# ciclo_V2.net
KiCad netlist of a schematic drawn in Altium Designer
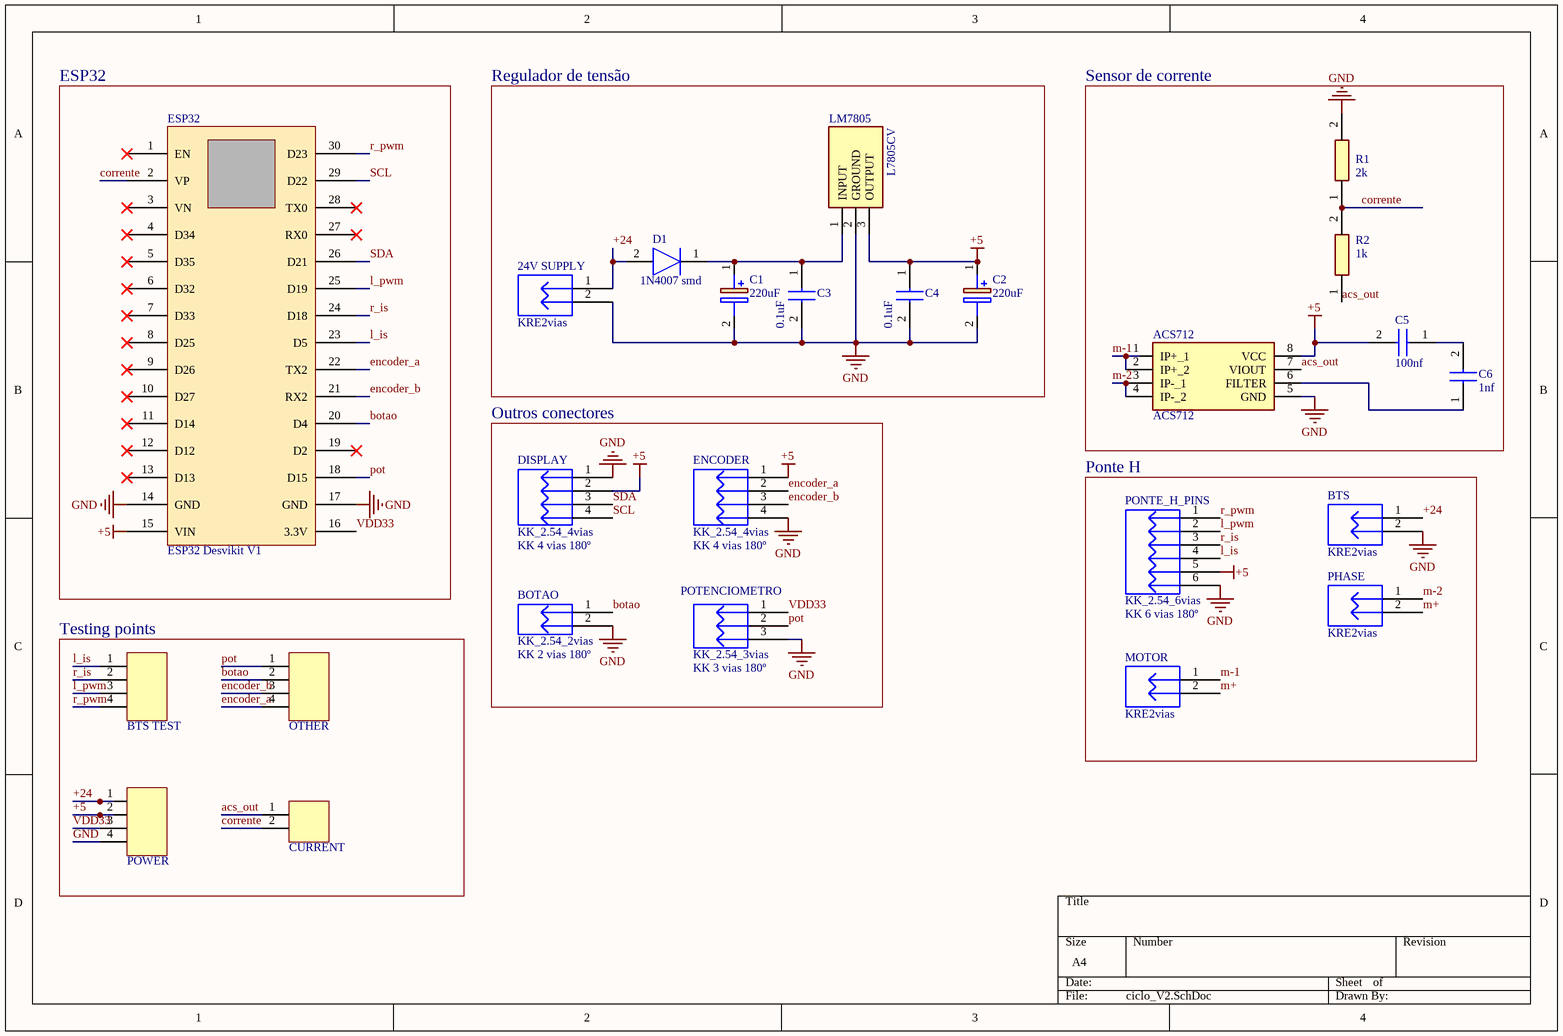
[diagram p0: ciclo_V2.SchDoc]

(export (version "E")
  (design (tool "Eeschema 10.0.6"))
  (components
    (comp (ref "24V SUPPLY")
      (value "KRE2vias")
      (footprint "KRE2-2vias")
      (description "Conector 2 vias")
      (libsource (lib "cicloV2_lib") (part "KRE2vias"))
    )
    (comp (ref "ACS712")
      (value "ACS712")
      (footprint "SOIC127P600X175-8N")
      (description "Sensor de corrente 20A")
      (fields (field (name "MANUFACTURER_PART_NUMBER") "ACS712ELCTR-05B-T"))
      (libsource (lib "cicloV2_lib") (part "ACS712"))
    )
    (comp (ref "BOTAO")
      (value "KK_2.54_2vias")
      (footprint "KK_2VIAS_180")
      (description "Conector KK 2.54mm 2 vias")
      (fields (field (name "VALOR") "KK 2 vias 180º"))
      (libsource (lib "cicloV2_lib") (part "KK_2.54_2vias"))
    )
    (comp (ref "BTS")
      (value "KRE2vias")
      (footprint "KRE2-2vias")
      (description "Conector 2 vias")
      (libsource (lib "cicloV2_lib") (part "KRE2vias"))
    )
    (comp (ref "BTS TEST")
      (value "Testing PADS 1x4")
      (footprint "Testing PADS 1x4")
      (description "Headers & Wire Housings 40Pin 2mm Spacing Single Row Hdrs, 5pc")
      (fields (field (name "MANUFACTURER") "Cromax"))
      (libsource (lib "cicloV2_lib") (part "Testing PADS 1x4"))
    )
    (comp (ref "C1")
      (value "220uF")
      (footprint "CAPPRD200W55D500H1200")
      (description "Capacitor Polarised")
      (fields
        (field (name "MANUFACTURER_PART_NUMBER") "ECA-0JM221")
        (field (name "MOUSER PART NUMBER") "667-ECA-0JM221")
      )
      (libsource (lib "cicloV2_lib") (part "Capacitor eletrolítico D5mm"))
    )
    (comp (ref "C2")
      (value "220uF")
      (footprint "CAPPRD200W55D500H1200")
      (description "Capacitor Polarised")
      (fields
        (field (name "MANUFACTURER_PART_NUMBER") "ECA-0JM221")
        (field (name "MOUSER PART NUMBER") "667-ECA-0JM221")
      )
      (libsource (lib "cicloV2_lib") (part "Capacitor eletrolítico D5mm"))
    )
    (comp (ref "C3")
      (value "0.1uF")
      (footprint "CAPC3216X180N")
      (description "Capacitor cerâmico SMD")
      (fields
        (field (name "MANUFACTURER_PART_NUMBER") "GRM31CC80E227ME11L")
        (field (name "MOUSER PART NUMBER") "81-GRM31CC80E227ME1L")
      )
      (libsource (lib "cicloV2_lib") (part "GRM31CC80E227ME11L"))
    )
    (comp (ref "C4")
      (value "0.1uF")
      (footprint "CAPC3216X180N")
      (description "Capacitor cerâmico SMD")
      (fields
        (field (name "MANUFACTURER_PART_NUMBER") "GRM31CC80E227ME11L")
        (field (name "MOUSER PART NUMBER") "81-GRM31CC80E227ME1L")
      )
      (libsource (lib "cicloV2_lib") (part "GRM31CC80E227ME11L"))
    )
    (comp (ref "C5")
      (value "100nf")
      (footprint "CAPC3216X180N")
      (description "Capacitor cerâmico SMD")
      (fields
        (field (name "MANUFACTURER_PART_NUMBER") "GRM31CC80E227ME11L")
        (field (name "MOUSER PART NUMBER") "81-GRM31CC80E227ME1L")
      )
      (libsource (lib "cicloV2_lib") (part "GRM31CC80E227ME11L"))
    )
    (comp (ref "C6")
      (value "1nf")
      (footprint "CAPC3216X180N")
      (description "Capacitor cerâmico SMD")
      (fields
        (field (name "MANUFACTURER_PART_NUMBER") "GRM31CC80E227ME11L")
        (field (name "MOUSER PART NUMBER") "81-GRM31CC80E227ME1L")
      )
      (libsource (lib "cicloV2_lib") (part "GRM31CC80E227ME11L"))
    )
    (comp (ref "CURRENT")
      (value "Testing PADS 1x2")
      (footprint "Testing PADS 1x2")
      (description "Headers & Wire Housings 40Pin 2mm Spacing Single Row Hdrs, 5pc")
      (fields (field (name "MANUFACTURER") "Cromax"))
      (libsource (lib "cicloV2_lib") (part "Testing PADS 1x2"))
    )
    (comp (ref "D1")
      (value "1N4007 smd")
      (footprint "cicloV2_lib:DIOM5327X242N")
      (description "Diode smd")
      (fields (field (name "MANUFACTURER_PART_NUMBER") "1N4007"))
      (libsource (lib "cicloV2_lib") (part "1N4007 smd"))
    )
    (comp (ref "DISPLAY")
      (value "KK_2.54_4vias")
      (footprint "KK_4vias_180")
      (description "Conector KK 2.54mm 4 vias")
      (fields (field (name "VALOR") "KK 4 vias 180º"))
      (libsource (lib "cicloV2_lib") (part "KK_2.54_4vias"))
    )
    (comp (ref "ENCODER")
      (value "KK_2.54_4vias")
      (footprint "KK_4vias_180")
      (description "Conector KK 2.54mm 4 vias")
      (fields (field (name "VALOR") "KK 4 vias 180º"))
      (libsource (lib "cicloV2_lib") (part "KK_2.54_4vias"))
    )
    (comp (ref "ESP32")
      (value "ESP32 Desvikit V1")
      (footprint "ESP32_Desvikit_v1")
      (description "microcontrolador com modulo bluetooth e wifi")
      (fields (field (name "Comment") "microcontrolador"))
      (libsource (lib "cicloV2_lib") (part "ESP32 Desvikit v1"))
    )
    (comp (ref "LM7805")
      (value "L7805CV")
      (footprint "TO255P460X1020X2008-3P")
      (description "Regulador de tensão para 5V")
      (fields (field (name "MOUSER PART NUMBER") "511-L7805CV"))
      (libsource (lib "cicloV2_lib") (part "L7805CV"))
    )
    (comp (ref "MOTOR")
      (value "KRE2vias")
      (footprint "KRE2-2vias")
      (description "Conector 2 vias")
      (libsource (lib "cicloV2_lib") (part "KRE2vias"))
    )
    (comp (ref "OTHER")
      (value "Testing PADS 1x4")
      (footprint "Testing PADS 1x4")
      (description "Headers & Wire Housings 40Pin 2mm Spacing Single Row Hdrs, 5pc")
      (fields (field (name "MANUFACTURER") "Cromax"))
      (libsource (lib "cicloV2_lib") (part "Testing PADS 1x4"))
    )
    (comp (ref "PHASE")
      (value "KRE2vias")
      (footprint "KRE2-2vias")
      (description "Conector 2 vias")
      (libsource (lib "cicloV2_lib") (part "KRE2vias"))
    )
    (comp (ref "PONTE_H_PINS")
      (value "KK_2.54_6vias")
      (footprint "KK_6vias_180")
      (description "Conector KK 2.54mm 6 vias")
      (fields (field (name "VALOR") "KK 6 vias 180º"))
      (libsource (lib "cicloV2_lib") (part "KK_2.54_6vias"))
    )
    (comp (ref "POTENCIOMETRO")
      (value "KK_2.54_3vias")
      (footprint "KK_3vias_180")
      (description "Conector KK 2.54mm 3 vias")
      (fields (field (name "VALOR") "KK 3 vias 180º"))
      (libsource (lib "cicloV2_lib") (part "KK_2.54_3vias"))
    )
    (comp (ref "POWER")
      (value "Testing PADS 1x4")
      (footprint "Testing PADS 1x4")
      (description "Headers & Wire Housings 40Pin 2mm Spacing Single Row Hdrs, 5pc")
      (fields (field (name "MANUFACTURER") "Cromax"))
      (libsource (lib "cicloV2_lib") (part "Testing PADS 1x4"))
    )
    (comp (ref "R1")
      (value "2k")
      (footprint "SamacSys:RESC3216X75N")
      (description "Resistor SMD 1206")
      (fields
        (field (name "MANUFACTURER_PART_NUMBER") "CR1206-F/-2R00ELF")
        (field (name "MOUSER PART NUMBER") "652-CR1206-F/2R00ELF")
      )
      (libsource (lib "cicloV2_lib") (part "CR1206"))
    )
    (comp (ref "R2")
      (value "1k")
      (footprint "SamacSys:RESC3216X75N")
      (description "Resistor SMD 1206")
      (fields
        (field (name "MANUFACTURER_PART_NUMBER") "CR1206-F/-2R00ELF")
        (field (name "MOUSER PART NUMBER") "652-CR1206-F/2R00ELF")
      )
      (libsource (lib "cicloV2_lib") (part "CR1206"))
    )
  )
  (nets
    (net (code "1") (name "+5") (class "Default")
      (node (ref "ACS712") (pin "8") (pinfunction "VCC_8") (pintype "passive"))
      (node (ref "C2") (pin "1") (pinfunction "+_1") (pintype "passive"))
      (node (ref "C4") (pin "1") (pinfunction "1_1") (pintype "passive"))
      (node (ref "C5") (pin "2") (pinfunction "2_2") (pintype "passive"))
      (node (ref "DISPLAY") (pin "2") (pintype "passive"))
      (node (ref "ENCODER") (pin "1") (pintype "passive"))
      (node (ref "ESP32") (pin "15") (pinfunction "VIN_15") (pintype "passive"))
      (node (ref "LM7805") (pin "3") (pinfunction "OUTPUT_3") (pintype "passive"))
      (node (ref "PONTE_H_PINS") (pin "5") (pintype "passive"))
      (node (ref "POWER") (pin "2") (pintype "passive"))
    )
    (net (code "2") (name "/+24") (class "Default")
      (node (ref "24V SUPPLY") (pin "1") (pintype "passive"))
      (node (ref "BTS") (pin "1") (pintype "passive"))
      (node (ref "D1") (pin "2") (pinfunction "A_2") (pintype "passive"))
      (node (ref "POWER") (pin "1") (pintype "passive"))
    )
    (net (code "3") (name "/SCL") (class "Default")
      (node (ref "DISPLAY") (pin "4") (pintype "passive"))
      (node (ref "ESP32") (pin "29") (pinfunction "D22_29") (pintype "passive"))
    )
    (net (code "4") (name "/SDA") (class "Default")
      (node (ref "DISPLAY") (pin "3") (pintype "passive"))
      (node (ref "ESP32") (pin "26") (pinfunction "D21_26") (pintype "passive"))
    )
    (net (code "5") (name "/VDD33") (class "Default")
      (node (ref "ESP32") (pin "16") (pinfunction "3.3V_16") (pintype "passive"))
      (node (ref "POTENCIOMETRO") (pin "1") (pintype "passive"))
      (node (ref "POWER") (pin "3") (pintype "passive"))
    )
    (net (code "6") (name "/acs_out") (class "Default")
      (node (ref "ACS712") (pin "7") (pinfunction "VIOUT_7") (pintype "passive"))
      (node (ref "CURRENT") (pin "1") (pintype "passive"))
      (node (ref "R2") (pin "1") (pinfunction "1_1") (pintype "passive"))
    )
    (net (code "7") (name "/botao") (class "Default")
      (node (ref "BOTAO") (pin "1") (pintype "passive"))
      (node (ref "ESP32") (pin "20") (pinfunction "D4_20") (pintype "passive"))
      (node (ref "OTHER") (pin "2") (pintype "passive"))
    )
    (net (code "8") (name "/corrente") (class "Default")
      (node (ref "CURRENT") (pin "2") (pintype "passive"))
      (node (ref "ESP32") (pin "2") (pinfunction "VP_2") (pintype "passive"))
      (node (ref "R1") (pin "1") (pinfunction "1_1") (pintype "passive"))
      (node (ref "R2") (pin "2") (pinfunction "2_2") (pintype "passive"))
    )
    (net (code "9") (name "/encoder_a") (class "Default")
      (node (ref "ENCODER") (pin "2") (pintype "passive"))
      (node (ref "ESP32") (pin "22") (pinfunction "TX2_22") (pintype "passive"))
      (node (ref "OTHER") (pin "4") (pintype "passive"))
    )
    (net (code "10") (name "/encoder_b") (class "Default")
      (node (ref "ENCODER") (pin "3") (pintype "passive"))
      (node (ref "ESP32") (pin "21") (pinfunction "RX2_21") (pintype "passive"))
      (node (ref "OTHER") (pin "3") (pintype "passive"))
    )
    (net (code "11") (name "/l_is") (class "Default")
      (node (ref "BTS TEST") (pin "1") (pintype "passive"))
      (node (ref "ESP32") (pin "23") (pinfunction "D5_23") (pintype "passive"))
      (node (ref "PONTE_H_PINS") (pin "4") (pintype "passive"))
    )
    (net (code "12") (name "/l_pwm") (class "Default")
      (node (ref "BTS TEST") (pin "3") (pintype "passive"))
      (node (ref "ESP32") (pin "25") (pinfunction "D19_25") (pintype "passive"))
      (node (ref "PONTE_H_PINS") (pin "2") (pintype "passive"))
    )
    (net (code "13") (name "/m+") (class "Default")
      (node (ref "MOTOR") (pin "2") (pintype "passive"))
      (node (ref "PHASE") (pin "2") (pintype "passive"))
    )
    (net (code "14") (name "/m-1") (class "Default")
      (node (ref "ACS712") (pin "1") (pinfunction "IP+_1_1") (pintype "passive"))
      (node (ref "ACS712") (pin "2") (pinfunction "IP+_2_2") (pintype "passive"))
      (node (ref "MOTOR") (pin "1") (pintype "passive"))
    )
    (net (code "15") (name "/m-2") (class "Default")
      (node (ref "ACS712") (pin "3") (pinfunction "IP-_1_3") (pintype "passive"))
      (node (ref "ACS712") (pin "4") (pinfunction "IP-_2_4") (pintype "passive"))
      (node (ref "PHASE") (pin "1") (pintype "passive"))
    )
    (net (code "16") (name "/pot") (class "Default")
      (node (ref "ESP32") (pin "18") (pinfunction "D15_18") (pintype "passive"))
      (node (ref "OTHER") (pin "1") (pintype "passive"))
      (node (ref "POTENCIOMETRO") (pin "2") (pintype "passive"))
    )
    (net (code "17") (name "/r_is") (class "Default")
      (node (ref "BTS TEST") (pin "2") (pintype "passive"))
      (node (ref "ESP32") (pin "24") (pinfunction "D18_24") (pintype "passive"))
      (node (ref "PONTE_H_PINS") (pin "3") (pintype "passive"))
    )
    (net (code "18") (name "/r_pwm") (class "Default")
      (node (ref "BTS TEST") (pin "4") (pintype "passive"))
      (node (ref "ESP32") (pin "30") (pinfunction "D23_30") (pintype "passive"))
      (node (ref "PONTE_H_PINS") (pin "1") (pintype "passive"))
    )
    (net (code "19") (name "GND") (class "Default")
      (node (ref "24V SUPPLY") (pin "2") (pintype "passive"))
      (node (ref "ACS712") (pin "5") (pinfunction "GND_5") (pintype "passive"))
      (node (ref "BOTAO") (pin "2") (pintype "passive"))
      (node (ref "BTS") (pin "2") (pintype "passive"))
      (node (ref "C1") (pin "2") (pinfunction "-_2") (pintype "passive"))
      (node (ref "C2") (pin "2") (pinfunction "-_2") (pintype "passive"))
      (node (ref "C3") (pin "2") (pinfunction "2_2") (pintype "passive"))
      (node (ref "C4") (pin "2") (pinfunction "2_2") (pintype "passive"))
      (node (ref "DISPLAY") (pin "1") (pintype "passive"))
      (node (ref "ENCODER") (pin "4") (pintype "passive"))
      (node (ref "ESP32") (pin "14") (pinfunction "GND_14") (pintype "passive"))
      (node (ref "ESP32") (pin "17") (pinfunction "GND_17") (pintype "passive"))
      (node (ref "LM7805") (pin "2") (pinfunction "GROUND_2") (pintype "passive"))
      (node (ref "PONTE_H_PINS") (pin "6") (pintype "passive"))
      (node (ref "POTENCIOMETRO") (pin "3") (pintype "passive"))
      (node (ref "POWER") (pin "4") (pintype "passive"))
      (node (ref "R1") (pin "2") (pinfunction "2_2") (pintype "passive"))
    )
    (net (code "20") (name "Net-(ACS712-FILTER)") (class "Default")
      (node (ref "ACS712") (pin "6") (pinfunction "FILTER_6") (pintype "passive"))
      (node (ref "C6") (pin "1") (pinfunction "1_1") (pintype "passive"))
    )
    (net (code "21") (name "Net-(C1-+)") (class "Default")
      (node (ref "C1") (pin "1") (pinfunction "+_1") (pintype "passive"))
      (node (ref "C3") (pin "1") (pinfunction "1_1") (pintype "passive"))
      (node (ref "D1") (pin "1") (pinfunction "K_1") (pintype "passive"))
      (node (ref "LM7805") (pin "1") (pinfunction "INPUT_1") (pintype "passive"))
    )
    (net (code "22") (name "Net-(C5-Pad1)") (class "Default")
      (node (ref "C5") (pin "1") (pinfunction "1_1") (pintype "passive"))
      (node (ref "C6") (pin "2") (pinfunction "2_2") (pintype "passive"))
    )
    (net (code "23") (name "unconnected-(ESP32-D2-Pad19)") (class "Default")
      (node (ref "ESP32") (pin "19") (pinfunction "D2_19") (pintype "passive+no_connect"))
    )
    (net (code "24") (name "unconnected-(ESP32-D12-Pad12)") (class "Default")
      (node (ref "ESP32") (pin "12") (pinfunction "D12_12") (pintype "passive+no_connect"))
    )
    (net (code "25") (name "unconnected-(ESP32-D13-Pad13)") (class "Default")
      (node (ref "ESP32") (pin "13") (pinfunction "D13_13") (pintype "passive+no_connect"))
    )
    (net (code "26") (name "unconnected-(ESP32-D14-Pad11)") (class "Default")
      (node (ref "ESP32") (pin "11") (pinfunction "D14_11") (pintype "passive+no_connect"))
    )
    (net (code "27") (name "unconnected-(ESP32-D25-Pad8)") (class "Default")
      (node (ref "ESP32") (pin "8") (pinfunction "D25_8") (pintype "passive+no_connect"))
    )
    (net (code "28") (name "unconnected-(ESP32-D26-Pad9)") (class "Default")
      (node (ref "ESP32") (pin "9") (pinfunction "D26_9") (pintype "passive+no_connect"))
    )
    (net (code "29") (name "unconnected-(ESP32-D27-Pad10)") (class "Default")
      (node (ref "ESP32") (pin "10") (pinfunction "D27_10") (pintype "passive+no_connect"))
    )
    (net (code "30") (name "unconnected-(ESP32-D32-Pad6)") (class "Default")
      (node (ref "ESP32") (pin "6") (pinfunction "D32_6") (pintype "passive+no_connect"))
    )
    (net (code "31") (name "unconnected-(ESP32-D33-Pad7)") (class "Default")
      (node (ref "ESP32") (pin "7") (pinfunction "D33_7") (pintype "passive+no_connect"))
    )
    (net (code "32") (name "unconnected-(ESP32-D34-Pad4)") (class "Default")
      (node (ref "ESP32") (pin "4") (pinfunction "D34_4") (pintype "passive+no_connect"))
    )
    (net (code "33") (name "unconnected-(ESP32-D35-Pad5)") (class "Default")
      (node (ref "ESP32") (pin "5") (pinfunction "D35_5") (pintype "passive+no_connect"))
    )
    (net (code "34") (name "unconnected-(ESP32-EN-Pad1)") (class "Default")
      (node (ref "ESP32") (pin "1") (pinfunction "EN_1") (pintype "passive+no_connect"))
    )
    (net (code "35") (name "unconnected-(ESP32-RX0-Pad27)") (class "Default")
      (node (ref "ESP32") (pin "27") (pinfunction "RX0_27") (pintype "passive+no_connect"))
    )
    (net (code "36") (name "unconnected-(ESP32-TX0-Pad28)") (class "Default")
      (node (ref "ESP32") (pin "28") (pinfunction "TX0_28") (pintype "passive+no_connect"))
    )
    (net (code "37") (name "unconnected-(ESP32-VN-Pad3)") (class "Default")
      (node (ref "ESP32") (pin "3") (pinfunction "VN_3") (pintype "passive+no_connect"))
    )
  )
)
